# boxiangf-TH.net
KiCad netlist of a schematic drawn in EAGLE
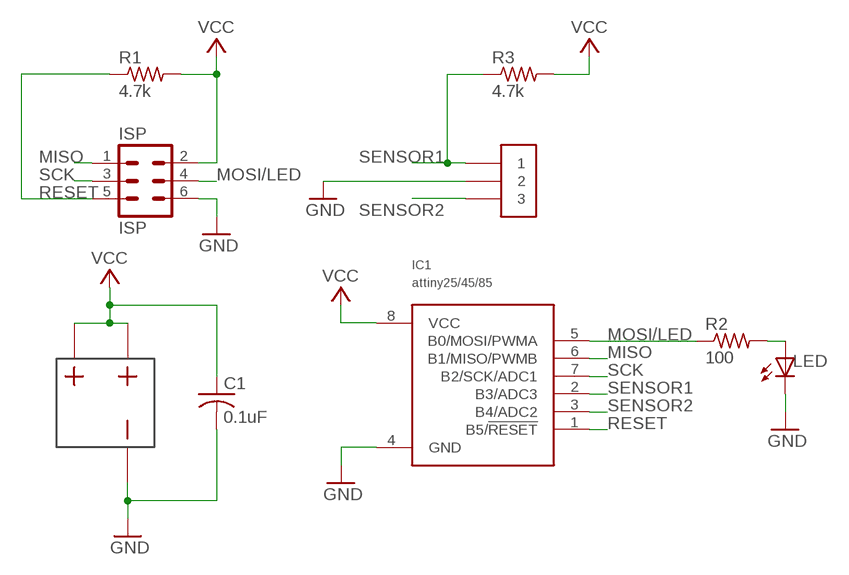
[diagram p0: schematic, sheet 1]

(export (version "E")
  (design (tool "Eeschema 10.0.6"))
  (components
    (comp (ref "C1")
      (value "0.1uF")
      (footprint "eagle-import:C025-025X050")
      (libsource (lib "eagle-import") (part "CAPACITORTH_CAP"))
    )
    (comp (ref "IC1")
      (value "attiny25/45/85")
      (footprint "eagle-import:DIL08")
      (libsource (lib "eagle-import") (part "ATTINY25TH_ATTINY"))
    )
    (comp (ref "ISP")
      (value "ISP")
      (footprint "eagle-import:6P2R0.1IN")
      (libsource (lib "eagle-import") (part "6PINCON_ISPTH_6PIN"))
    )
    (comp (ref "LED")
      (value "LEDTH_LED")
      (footprint "eagle-import:LED5MM")
      (libsource (lib "eagle-import") (part "LEDTH_LED"))
    )
    (comp (ref "R1")
      (value "4.7k")
      (footprint "eagle-import:0204_7")
      (libsource (lib "eagle-import") (part "RESISTORTH_RESISTOR"))
    )
    (comp (ref "R2")
      (value "100")
      (footprint "eagle-import:0204_7")
      (libsource (lib "eagle-import") (part "RESISTORTH_RESISTOR"))
    )
    (comp (ref "R3")
      (value "4.7k")
      (footprint "eagle-import:0204_7")
      (libsource (lib "eagle-import") (part "RESISTORTH_RESISTOR"))
    )
    (comp (ref "SENSE")
      (value "3PINCONTH_3PIN")
      (footprint "eagle-import:PUSHCON3")
      (libsource (lib "eagle-import") (part "3PINCONTH_3PIN"))
    )
    (comp (ref "US1")
      (value "BATTERYTH_BA2032")
      (footprint "eagle-import:BA2032")
      (libsource (lib "eagle-import") (part "BATTERYTH_BA2032"))
    )
  )
  (nets
    (net (code "1") (name "/MISO") (class "Default")
      (node (ref "IC1") (pin "6") (pinfunction "B1/MISO/PWMB_6") (pintype "bidirectional"))
      (node (ref "ISP") (pin "1") (pinfunction "1_1") (pintype "bidirectional"))
    )
    (net (code "2") (name "/MOSI{slash}LED") (class "Default")
      (node (ref "IC1") (pin "5") (pinfunction "B0/MOSI/PWMA_5") (pintype "bidirectional"))
      (node (ref "ISP") (pin "4") (pinfunction "4_4") (pintype "bidirectional"))
      (node (ref "R2") (pin "1") (pinfunction "1_1") (pintype "bidirectional"))
    )
    (net (code "3") (name "/RESET") (class "Default")
      (node (ref "IC1") (pin "1") (pinfunction "B5/~{RESET}_1") (pintype "bidirectional"))
      (node (ref "ISP") (pin "5") (pinfunction "5_5") (pintype "bidirectional"))
      (node (ref "R1") (pin "1") (pinfunction "1_1") (pintype "bidirectional"))
    )
    (net (code "4") (name "/SCK") (class "Default")
      (node (ref "IC1") (pin "7") (pinfunction "B2/SCK/ADC1_7") (pintype "bidirectional"))
      (node (ref "ISP") (pin "3") (pinfunction "3_3") (pintype "bidirectional"))
    )
    (net (code "5") (name "/SENSOR1") (class "Default")
      (node (ref "IC1") (pin "2") (pinfunction "B3/ADC3_2") (pintype "bidirectional"))
      (node (ref "R3") (pin "1") (pinfunction "1_1") (pintype "bidirectional"))
      (node (ref "SENSE") (pin "1") (pinfunction "1_1") (pintype "bidirectional"))
    )
    (net (code "6") (name "/SENSOR2") (class "Default")
      (node (ref "IC1") (pin "3") (pinfunction "B4/ADC2_3") (pintype "bidirectional"))
      (node (ref "SENSE") (pin "3") (pinfunction "3_3") (pintype "bidirectional"))
    )
    (net (code "7") (name "GND") (class "Default")
      (node (ref "C1") (pin "2") (pinfunction "2_2") (pintype "bidirectional"))
      (node (ref "IC1") (pin "4") (pinfunction "GND_4") (pintype "bidirectional"))
      (node (ref "ISP") (pin "6") (pinfunction "6_6") (pintype "bidirectional"))
      (node (ref "LED") (pin "K") (pinfunction "C_K") (pintype "bidirectional"))
      (node (ref "SENSE") (pin "2") (pinfunction "2_2") (pintype "bidirectional"))
      (node (ref "US1") (pin "P$1") (pinfunction "P$1_P$1") (pintype "bidirectional"))
    )
    (net (code "8") (name "Net-(LED-PadA)") (class "Default")
      (node (ref "LED") (pin "A") (pinfunction "A_A") (pintype "bidirectional"))
      (node (ref "R2") (pin "2") (pinfunction "2_2") (pintype "bidirectional"))
    )
    (net (code "9") (name "VCC") (class "Default")
      (node (ref "C1") (pin "1") (pinfunction "1_1") (pintype "bidirectional"))
      (node (ref "IC1") (pin "8") (pinfunction "VCC_8") (pintype "bidirectional"))
      (node (ref "ISP") (pin "2") (pinfunction "2_2") (pintype "bidirectional"))
      (node (ref "R1") (pin "2") (pinfunction "2_2") (pintype "bidirectional"))
      (node (ref "R3") (pin "2") (pinfunction "2_2") (pintype "bidirectional"))
      (node (ref "US1") (pin "P$2") (pinfunction "P$2_P$2") (pintype "bidirectional"))
      (node (ref "US1") (pin "P$3") (pinfunction "P$3_P$3") (pintype "bidirectional"))
    )
  )
)
